# MPU-9250-mbed_rev02.net
KiCad netlist of a schematic drawn in EAGLE
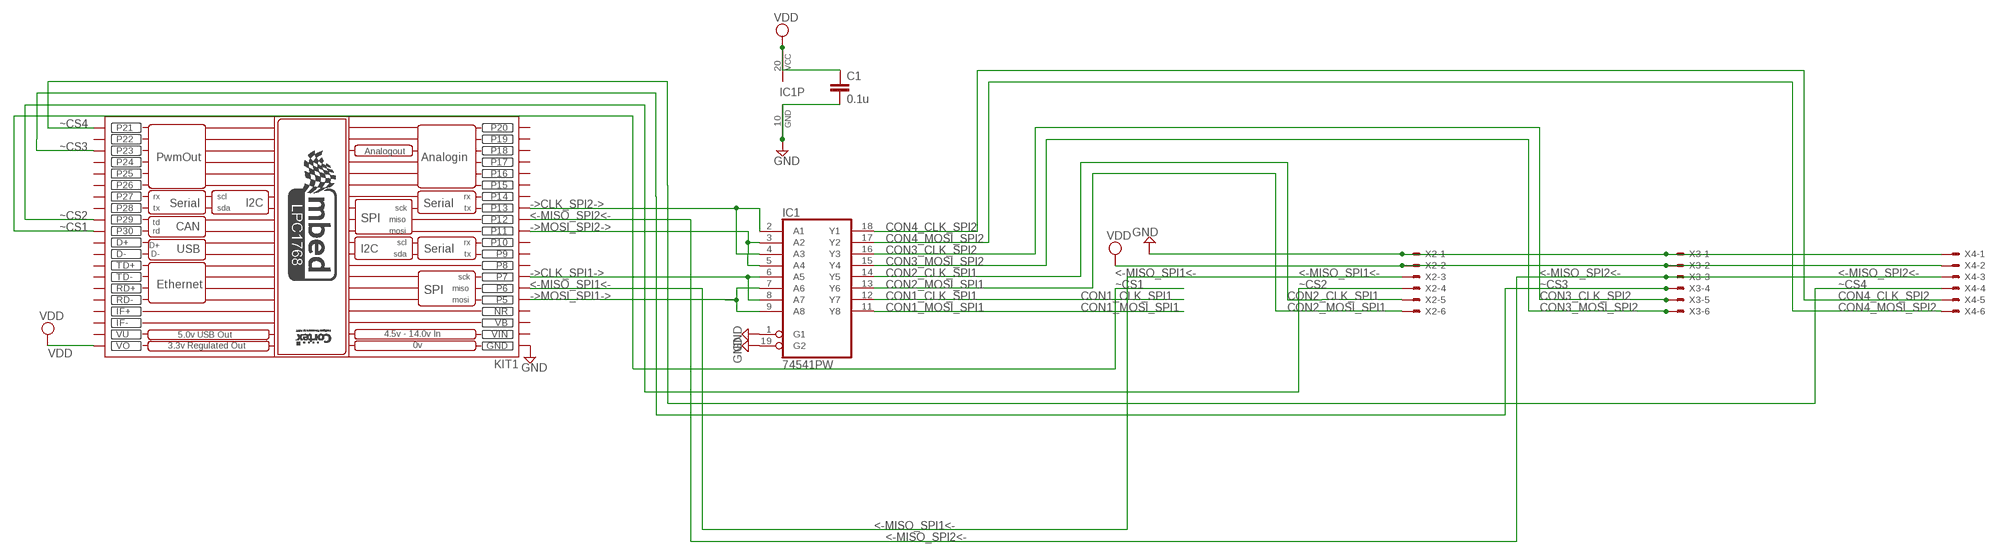
[diagram p0: schematic, sheet 1]

(export (version "E")
  (design (tool "Eeschema 10.0.6"))
  (components
    (comp (ref "C1")
      (value "0.1u")
      (footprint "eagle-import:C5B3")
      (libsource (lib "eagle-import") (part "C5/3"))
    )
    (comp (ref "IC1")
      (value "74541PW")
      (footprint "eagle-import:TSSOP20")
      (libsource (lib "eagle-import") (part "74541PW"))
    )
    (comp (ref "KIT1")
      (value "MBED_NXP_LPC1768")
      (footprint "eagle-import:MBED-KIT")
      (libsource (lib "eagle-import") (part "MBED_NXP_LPC1768"))
    )
    (comp (ref "X2")
      (value "22-23-2061")
      (footprint "eagle-import:22-23-2061")
      (fields (field (name "MF") "MOLEX"))
      (libsource (lib "eagle-import") (part "22-23-2061"))
    )
    (comp (ref "X3")
      (value "22-23-2061")
      (footprint "eagle-import:22-23-2061")
      (fields (field (name "MF") "MOLEX"))
      (libsource (lib "eagle-import") (part "22-23-2061"))
    )
    (comp (ref "X4")
      (value "22-23-2061")
      (footprint "eagle-import:22-23-2061")
      (fields (field (name "MF") "MOLEX"))
      (libsource (lib "eagle-import") (part "22-23-2061"))
    )
  )
  (nets
    (net (code "1") (name "/->CLK_SPI1->") (class "Default")
      (node (ref "IC1") (pin "6") (pinfunction "A5_6") (pintype "input"))
      (node (ref "IC1") (pin "8") (pinfunction "A7_8") (pintype "input"))
      (node (ref "KIT1") (pin "P$7") (pinfunction "P7_P$7") (pintype "bidirectional"))
    )
    (net (code "2") (name "/->CLK_SPI2->") (class "Default")
      (node (ref "IC1") (pin "2") (pinfunction "A1_2") (pintype "input"))
      (node (ref "IC1") (pin "4") (pinfunction "A3_4") (pintype "input"))
      (node (ref "KIT1") (pin "P$13") (pinfunction "P13_P$13") (pintype "bidirectional"))
    )
    (net (code "3") (name "/->MOSI_SPI1->") (class "Default")
      (node (ref "IC1") (pin "7") (pinfunction "A6_7") (pintype "input"))
      (node (ref "IC1") (pin "9") (pinfunction "A8_9") (pintype "input"))
      (node (ref "KIT1") (pin "P$5") (pinfunction "P5_P$5") (pintype "bidirectional"))
    )
    (net (code "4") (name "/->MOSI_SPI2->") (class "Default")
      (node (ref "IC1") (pin "3") (pinfunction "A2_3") (pintype "input"))
      (node (ref "IC1") (pin "5") (pinfunction "A4_5") (pintype "input"))
      (node (ref "KIT1") (pin "P$11") (pinfunction "P11_P$11") (pintype "bidirectional"))
    )
    (net (code "5") (name "/<-MISO_SPI1<-") (class "Default")
      (node (ref "KIT1") (pin "P$6") (pinfunction "P6_P$6") (pintype "bidirectional"))
      (node (ref "X2") (pin "3") (pinfunction "S_3") (pintype "passive"))
    )
    (net (code "6") (name "/<-MISO_SPI2<-") (class "Default")
      (node (ref "KIT1") (pin "P$12") (pinfunction "P12_P$12") (pintype "bidirectional"))
      (node (ref "X3") (pin "3") (pinfunction "S_3") (pintype "passive"))
      (node (ref "X4") (pin "3") (pinfunction "S_3") (pintype "passive"))
    )
    (net (code "7") (name "/CON1_CLK_SPI1") (class "Default")
      (node (ref "IC1") (pin "12") (pinfunction "Y7_12") (pintype "tri_state"))
    )
    (net (code "8") (name "/CON1_MOSI_SPI1") (class "Default")
      (node (ref "IC1") (pin "11") (pinfunction "Y8_11") (pintype "tri_state"))
    )
    (net (code "9") (name "/CON2_CLK_SPI1") (class "Default")
      (node (ref "IC1") (pin "14") (pinfunction "Y5_14") (pintype "tri_state"))
      (node (ref "X2") (pin "5") (pinfunction "S_5") (pintype "passive"))
    )
    (net (code "10") (name "/CON2_MOSI_SPI1") (class "Default")
      (node (ref "IC1") (pin "13") (pinfunction "Y6_13") (pintype "tri_state"))
      (node (ref "X2") (pin "6") (pinfunction "S_6") (pintype "passive"))
    )
    (net (code "11") (name "/CON3_CLK_SPI2") (class "Default")
      (node (ref "IC1") (pin "16") (pinfunction "Y3_16") (pintype "tri_state"))
      (node (ref "X3") (pin "5") (pinfunction "S_5") (pintype "passive"))
    )
    (net (code "12") (name "/CON3_MOSI_SPI2") (class "Default")
      (node (ref "IC1") (pin "15") (pinfunction "Y4_15") (pintype "tri_state"))
      (node (ref "X3") (pin "6") (pinfunction "S_6") (pintype "passive"))
    )
    (net (code "13") (name "/CON4_CLK_SPI2") (class "Default")
      (node (ref "IC1") (pin "18") (pinfunction "Y1_18") (pintype "tri_state"))
      (node (ref "X4") (pin "5") (pinfunction "S_5") (pintype "passive"))
    )
    (net (code "14") (name "/CON4_MOSI_SPI2") (class "Default")
      (node (ref "IC1") (pin "17") (pinfunction "Y2_17") (pintype "tri_state"))
      (node (ref "X4") (pin "6") (pinfunction "S_6") (pintype "passive"))
    )
    (net (code "15") (name "/NR") (class "Default")
      (node (ref "KIT1") (pin "NR") (pinfunction "NR_NR") (pintype "power_in"))
    )
    (net (code "16") (name "/VB") (class "Default")
      (node (ref "KIT1") (pin "VB") (pinfunction "VB_VB") (pintype "power_in"))
    )
    (net (code "17") (name "/VIN") (class "Default")
      (node (ref "KIT1") (pin "VIN") (pinfunction "VIN_VIN") (pintype "power_in"))
    )
    (net (code "18") (name "/VU") (class "Default")
      (node (ref "KIT1") (pin "VU") (pinfunction "VU_VU") (pintype "power_in"))
    )
    (net (code "19") (name "/~{CS1}") (class "Default")
      (node (ref "KIT1") (pin "P$30") (pinfunction "P30_P$30") (pintype "bidirectional"))
    )
    (net (code "20") (name "/~{CS2}") (class "Default")
      (node (ref "KIT1") (pin "P$29") (pinfunction "P29_P$29") (pintype "bidirectional"))
      (node (ref "X2") (pin "4") (pinfunction "S_4") (pintype "passive"))
    )
    (net (code "21") (name "/~{CS3}") (class "Default")
      (node (ref "KIT1") (pin "P$23") (pinfunction "P23_P$23") (pintype "bidirectional"))
      (node (ref "X3") (pin "4") (pinfunction "S_4") (pintype "passive"))
    )
    (net (code "22") (name "/~{CS4}") (class "Default")
      (node (ref "KIT1") (pin "P$21") (pinfunction "P21_P$21") (pintype "bidirectional"))
      (node (ref "X4") (pin "4") (pinfunction "S_4") (pintype "passive"))
    )
    (net (code "23") (name "GND") (class "Default")
      (node (ref "C1") (pin "2") (pinfunction "2_2") (pintype "passive"))
      (node (ref "IC1") (pin "1") (pinfunction "G1_1") (pintype "input"))
      (node (ref "IC1") (pin "10") (pinfunction "GND_10") (pintype "power_in"))
      (node (ref "IC1") (pin "19") (pinfunction "G2_19") (pintype "input"))
      (node (ref "KIT1") (pin "GND") (pinfunction "GND_GND") (pintype "power_in"))
      (node (ref "X2") (pin "1") (pinfunction "S_1") (pintype "passive"))
      (node (ref "X3") (pin "1") (pinfunction "S_1") (pintype "passive"))
      (node (ref "X4") (pin "1") (pinfunction "S_1") (pintype "passive"))
    )
    (net (code "24") (name "VDD") (class "Default")
      (node (ref "C1") (pin "1") (pinfunction "1_1") (pintype "passive"))
      (node (ref "IC1") (pin "20") (pinfunction "VCC_20") (pintype "power_in"))
      (node (ref "KIT1") (pin "VOUT") (pinfunction "VO_VOUT") (pintype "power_in"))
      (node (ref "X2") (pin "2") (pinfunction "S_2") (pintype "passive"))
      (node (ref "X3") (pin "2") (pinfunction "S_2") (pintype "passive"))
      (node (ref "X4") (pin "2") (pinfunction "S_2") (pintype "passive"))
    )
    (net (code "25") (name "unconnected-(KIT1-P8-PadP$8)") (class "Default")
      (node (ref "KIT1") (pin "P$8") (pinfunction "P8_P$8") (pintype "bidirectional"))
    )
    (net (code "26") (name "unconnected-(KIT1-P9-PadP$9)") (class "Default")
      (node (ref "KIT1") (pin "P$9") (pinfunction "P9_P$9") (pintype "bidirectional"))
    )
    (net (code "27") (name "unconnected-(KIT1-P10-PadP$10)") (class "Default")
      (node (ref "KIT1") (pin "P$10") (pinfunction "P10_P$10") (pintype "bidirectional"))
    )
    (net (code "28") (name "unconnected-(KIT1-P14-PadP$14)") (class "Default")
      (node (ref "KIT1") (pin "P$14") (pinfunction "P14_P$14") (pintype "bidirectional"))
    )
    (net (code "29") (name "unconnected-(KIT1-P15-PadP$15)") (class "Default")
      (node (ref "KIT1") (pin "P$15") (pinfunction "P15_P$15") (pintype "bidirectional"))
    )
    (net (code "30") (name "unconnected-(KIT1-P16-PadP$16)") (class "Default")
      (node (ref "KIT1") (pin "P$16") (pinfunction "P16_P$16") (pintype "bidirectional"))
    )
    (net (code "31") (name "unconnected-(KIT1-P17-PadP$17)") (class "Default")
      (node (ref "KIT1") (pin "P$17") (pinfunction "P17_P$17") (pintype "bidirectional"))
    )
    (net (code "32") (name "unconnected-(KIT1-P18-PadP$18)") (class "Default")
      (node (ref "KIT1") (pin "P$18") (pinfunction "P18_P$18") (pintype "bidirectional"))
    )
    (net (code "33") (name "unconnected-(KIT1-P19-PadP$19)") (class "Default")
      (node (ref "KIT1") (pin "P$19") (pinfunction "P19_P$19") (pintype "bidirectional"))
    )
    (net (code "34") (name "unconnected-(KIT1-P20-PadP$20)") (class "Default")
      (node (ref "KIT1") (pin "P$20") (pinfunction "P20_P$20") (pintype "bidirectional"))
    )
    (net (code "35") (name "unconnected-(KIT1-P22-PadP$22)") (class "Default")
      (node (ref "KIT1") (pin "P$22") (pinfunction "P22_P$22") (pintype "bidirectional"))
    )
    (net (code "36") (name "unconnected-(KIT1-P24-PadP$24)") (class "Default")
      (node (ref "KIT1") (pin "P$24") (pinfunction "P24_P$24") (pintype "bidirectional"))
    )
    (net (code "37") (name "unconnected-(KIT1-P25-PadP$25)") (class "Default")
      (node (ref "KIT1") (pin "P$25") (pinfunction "P25_P$25") (pintype "bidirectional"))
    )
    (net (code "38") (name "unconnected-(KIT1-P26-PadP$26)") (class "Default")
      (node (ref "KIT1") (pin "P$26") (pinfunction "P26_P$26") (pintype "bidirectional"))
    )
    (net (code "39") (name "unconnected-(KIT1-P27-PadP$27)") (class "Default")
      (node (ref "KIT1") (pin "P$27") (pinfunction "P27_P$27") (pintype "bidirectional"))
    )
    (net (code "40") (name "unconnected-(KIT1-P28-PadP$28)") (class "Default")
      (node (ref "KIT1") (pin "P$28") (pinfunction "P28_P$28") (pintype "bidirectional"))
    )
    (net (code "41") (name "unconnected-(KIT1-PadD+)") (class "Default")
      (node (ref "KIT1") (pin "D+") (pinfunction "D+_D+") (pintype "bidirectional"))
    )
    (net (code "42") (name "unconnected-(KIT1-PadD-)") (class "Default")
      (node (ref "KIT1") (pin "D-") (pinfunction "D-_D-") (pintype "bidirectional"))
    )
    (net (code "43") (name "unconnected-(KIT1-PadIF+)") (class "Default")
      (node (ref "KIT1") (pin "IF+") (pinfunction "IF+_IF+") (pintype "bidirectional"))
    )
    (net (code "44") (name "unconnected-(KIT1-PadIF-)") (class "Default")
      (node (ref "KIT1") (pin "IF-") (pinfunction "IF-_IF-") (pintype "bidirectional"))
    )
    (net (code "45") (name "unconnected-(KIT1-PadRD+)") (class "Default")
      (node (ref "KIT1") (pin "RD+") (pinfunction "RD+_RD+") (pintype "bidirectional"))
    )
    (net (code "46") (name "unconnected-(KIT1-PadRD-)") (class "Default")
      (node (ref "KIT1") (pin "RD-") (pinfunction "RD-_RD-") (pintype "bidirectional"))
    )
    (net (code "47") (name "unconnected-(KIT1-PadTD+)") (class "Default")
      (node (ref "KIT1") (pin "TD+") (pinfunction "TD+_TD+") (pintype "bidirectional"))
    )
    (net (code "48") (name "unconnected-(KIT1-PadTD-)") (class "Default")
      (node (ref "KIT1") (pin "TD-") (pinfunction "TD-_TD-") (pintype "bidirectional"))
    )
  )
)
